# SCH_Temp-and-fan-ctrl_2026-02-23.net
KiCad netlist of a schematic drawn in EasyEDA
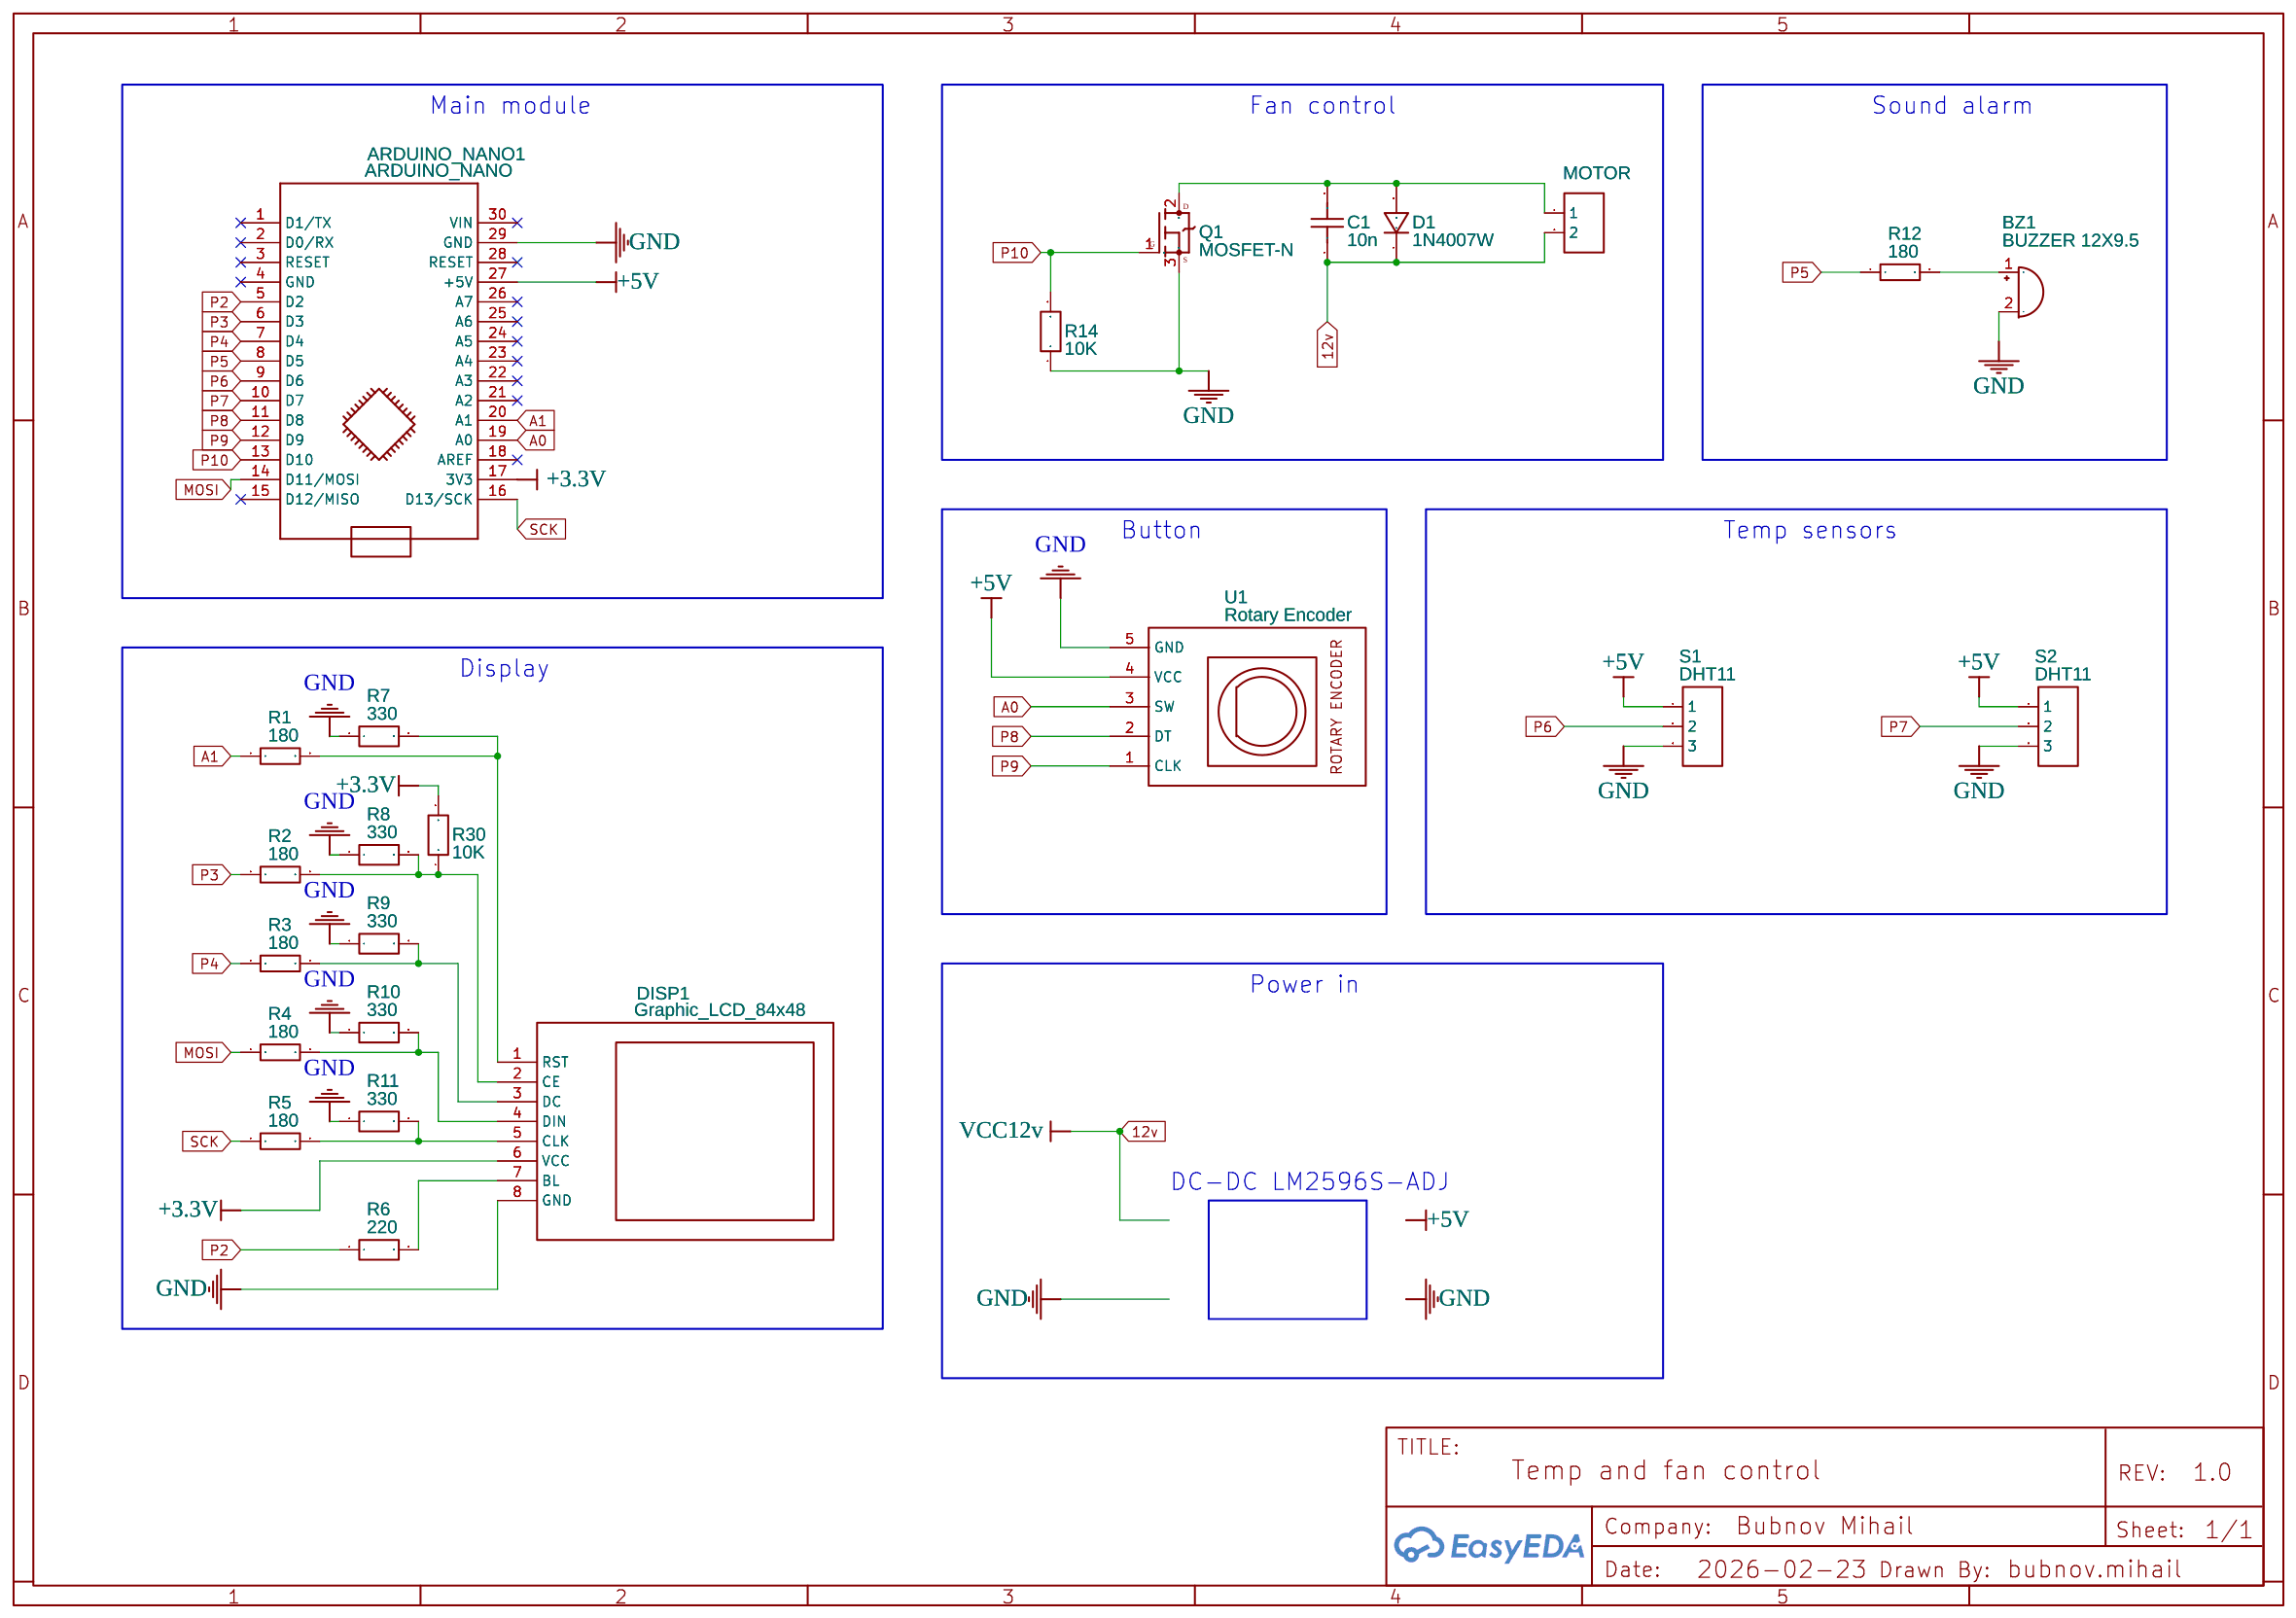
[diagram p0: schematic sheet]

(export (version "E")
  (design (tool "Eeschema 10.0.6"))
  (components
    (comp (ref "ARDUINO_NANO1") (value "ARDUINO_NANO") (libsource (lib "") (part "ARDUINO_NANO")))
    (comp (ref "BZ1") (value "BUZZER 12X9.5") (libsource (lib "") (part "BUZZER 12X9.5 FATHBOARD COPY")))
    (comp (ref "C1") (value "10n") (libsource (lib "") (part "C_0603_US")))
    (comp (ref "D1")
      (value "1N4007W")
      (fields (field (name "Manufacturer") "BLUE ROCKET"))
      (libsource (lib "") (part "1N4007W"))
    )
    (comp (ref "DISP1") (value "Graphic_LCD_84x48") (libsource (lib "") (part "Graphic_LCD_84x48")))
    (comp (ref "MOTOR") (value "1-") (libsource (lib "") (part "CONN-TH_2P-P5.00")))
    (comp (ref "Q1") (value "MOSFET-N") (libsource (lib "") (part "MOSFET-N")))
    (comp (ref "R1")
      (value "180")
      (fields (field (name "Manufacturer Part") "CFR02SJ0103A10") (field (name "Manufacturer") "UniOhm"))
      (libsource (lib "") (part "CFR02SJ0103A10"))
    )
    (comp (ref "R2")
      (value "180")
      (fields (field (name "Manufacturer Part") "CFR02SJ0103A10") (field (name "Manufacturer") "UniOhm"))
      (libsource (lib "") (part "CFR02SJ0103A10"))
    )
    (comp (ref "R3")
      (value "180")
      (fields (field (name "Manufacturer Part") "CFR02SJ0103A10") (field (name "Manufacturer") "UniOhm"))
      (libsource (lib "") (part "CFR02SJ0103A10"))
    )
    (comp (ref "R4")
      (value "180")
      (fields (field (name "Manufacturer Part") "CFR02SJ0103A10") (field (name "Manufacturer") "UniOhm"))
      (libsource (lib "") (part "CFR02SJ0103A10"))
    )
    (comp (ref "R5")
      (value "180")
      (fields (field (name "Manufacturer Part") "CFR02SJ0103A10") (field (name "Manufacturer") "UniOhm"))
      (libsource (lib "") (part "CFR02SJ0103A10"))
    )
    (comp (ref "R6")
      (value "220")
      (fields
        (field (name "Manufacturer Part") "RD 1/2WS 10K J T/B A1")
        (field (name "Manufacturer") "TyoHM")
      )
      (libsource (lib "") (part "RD 1/2WS 10K J T/B A1_1"))
    )
    (comp (ref "R7")
      (value "330")
      (fields
        (field (name "Manufacturer Part") "RD 1/2WS 10K J T/B A1")
        (field (name "Manufacturer") "TyoHM")
      )
      (libsource (lib "") (part "RD 1/2WS 10K J T/B A1_1"))
    )
    (comp (ref "R8")
      (value "330")
      (fields
        (field (name "Manufacturer Part") "RD 1/2WS 10K J T/B A1")
        (field (name "Manufacturer") "TyoHM")
      )
      (libsource (lib "") (part "RD 1/2WS 10K J T/B A1_1"))
    )
    (comp (ref "R9")
      (value "330")
      (fields
        (field (name "Manufacturer Part") "RD 1/2WS 10K J T/B A1")
        (field (name "Manufacturer") "TyoHM")
      )
      (libsource (lib "") (part "RD 1/2WS 10K J T/B A1_1"))
    )
    (comp (ref "R10")
      (value "330")
      (fields
        (field (name "Manufacturer Part") "RD 1/2WS 10K J T/B A1")
        (field (name "Manufacturer") "TyoHM")
      )
      (libsource (lib "") (part "RD 1/2WS 10K J T/B A1_1"))
    )
    (comp (ref "R11")
      (value "330")
      (fields
        (field (name "Manufacturer Part") "RD 1/2WS 10K J T/B A1")
        (field (name "Manufacturer") "TyoHM")
      )
      (libsource (lib "") (part "RD 1/2WS 10K J T/B A1_1"))
    )
    (comp (ref "R12")
      (value "180")
      (fields (field (name "Manufacturer Part") "CFR02SJ0103A10") (field (name "Manufacturer") "UniOhm"))
      (libsource (lib "") (part "CFR02SJ0103A10"))
    )
    (comp (ref "R14")
      (value "10K")
      (fields
        (field (name "Manufacturer Part") "RD 1/2WS 10K J T/B A1")
        (field (name "Manufacturer") "TyoHM")
      )
      (libsource (lib "") (part "RD 1/2WS 10K J T/B A1"))
    )
    (comp (ref "R30")
      (value "10K")
      (fields
        (field (name "Manufacturer Part") "RD 1/2WS 10K J T/B A1")
        (field (name "Manufacturer") "TyoHM")
      )
      (libsource (lib "") (part "RD 1/2WS 10K J T/B A1"))
    )
    (comp (ref "S1") (value "DHT11") (libsource (lib "") (part "HDR-F-2.54_1x3")))
    (comp (ref "S2") (value "DHT11") (libsource (lib "") (part "HDR-F-2.54_1x3")))
    (comp (ref "U1")
      (value "Rotary Encoder")
      (fields (field (name "Manufacturer Part") "KY-040"))
      (libsource (lib "") (part "Rotary Encoder"))
    )
  )
  (nets
    (net (code "1") (name "+3.3V") (class "Default")
      (node (ref "ARDUINO_NANO1") (pin "17") (pinfunction "3V3_17") (pintype "unspecified"))
      (node (ref "DISP1") (pin "6") (pinfunction "VCC_6") (pintype "passive"))
      (node (ref "R30") (pin "2") (pinfunction "2_2") (pintype "unspecified"))
    )
    (net (code "2") (name "+5V") (class "Default")
      (node (ref "ARDUINO_NANO1") (pin "27") (pinfunction "+5V_27") (pintype "unspecified"))
      (node (ref "S1") (pin "1") (pinfunction "1_1") (pintype "input"))
      (node (ref "S2") (pin "1") (pinfunction "1_1") (pintype "input"))
      (node (ref "U1") (pin "4") (pinfunction "VCC_4") (pintype "unspecified"))
    )
    (net (code "3") (name "12v") (class "Default")
      (node (ref "C1") (pin "1") (pinfunction "1_1") (pintype "unspecified"))
      (node (ref "D1") (pin "1") (pinfunction "1_1") (pintype "unspecified"))
      (node (ref "MOTOR") (pin "2") (pinfunction "2_2") (pintype "unspecified"))
    )
    (net (code "4") (name "A0") (class "Default")
      (node (ref "ARDUINO_NANO1") (pin "19") (pinfunction "A0_19") (pintype "unspecified"))
      (node (ref "U1") (pin "3") (pinfunction "SW_3") (pintype "unspecified"))
    )
    (net (code "5") (name "A1") (class "Default")
      (node (ref "ARDUINO_NANO1") (pin "20") (pinfunction "A1_20") (pintype "unspecified"))
      (node (ref "R1") (pin "1") (pinfunction "1_1") (pintype "input"))
    )
    (net (code "6") (name "GND") (class "Default")
      (node (ref "ARDUINO_NANO1") (pin "29") (pinfunction "GND_29") (pintype "unspecified"))
      (node (ref "BZ1") (pin "2") (pinfunction "-_2") (pintype "unspecified"))
      (node (ref "DISP1") (pin "8") (pinfunction "GND_8") (pintype "passive"))
      (node (ref "Q1") (pin "3") (pinfunction "S_3") (pintype "unspecified"))
      (node (ref "R10") (pin "1") (pinfunction "1_1") (pintype "unspecified"))
      (node (ref "R11") (pin "1") (pinfunction "1_1") (pintype "unspecified"))
      (node (ref "R14") (pin "1") (pinfunction "1_1") (pintype "unspecified"))
      (node (ref "R7") (pin "1") (pinfunction "1_1") (pintype "unspecified"))
      (node (ref "R8") (pin "1") (pinfunction "1_1") (pintype "unspecified"))
      (node (ref "R9") (pin "1") (pinfunction "1_1") (pintype "unspecified"))
      (node (ref "S1") (pin "3") (pinfunction "3_3") (pintype "input"))
      (node (ref "S2") (pin "3") (pinfunction "3_3") (pintype "input"))
      (node (ref "U1") (pin "5") (pinfunction "GND_5") (pintype "unspecified"))
    )
    (net (code "7") (name "MOSI") (class "Default")
      (node (ref "ARDUINO_NANO1") (pin "14") (pinfunction "D11/MOSI_14") (pintype "unspecified"))
      (node (ref "R4") (pin "1") (pinfunction "1_1") (pintype "input"))
    )
    (net (code "8") (name "Net-(BZ1-+)") (class "Default")
      (node (ref "BZ1") (pin "1") (pinfunction "+_1") (pintype "unspecified"))
      (node (ref "R12") (pin "2") (pinfunction "2_2") (pintype "input"))
    )
    (net (code "9") (name "Net-(DISP1-BL)") (class "Default")
      (node (ref "DISP1") (pin "7") (pinfunction "BL_7") (pintype "input"))
      (node (ref "R6") (pin "2") (pinfunction "2_2") (pintype "unspecified"))
    )
    (net (code "10") (name "Net-(DISP1-CE)") (class "Default")
      (node (ref "DISP1") (pin "2") (pinfunction "CE_2") (pintype "input"))
      (node (ref "R2") (pin "2") (pinfunction "2_2") (pintype "input"))
      (node (ref "R30") (pin "1") (pinfunction "1_1") (pintype "unspecified"))
      (node (ref "R8") (pin "2") (pinfunction "2_2") (pintype "unspecified"))
    )
    (net (code "11") (name "Net-(DISP1-CLK)") (class "Default")
      (node (ref "DISP1") (pin "5") (pinfunction "CLK_5") (pintype "input"))
      (node (ref "R11") (pin "2") (pinfunction "2_2") (pintype "unspecified"))
      (node (ref "R5") (pin "2") (pinfunction "2_2") (pintype "input"))
    )
    (net (code "12") (name "Net-(DISP1-DC)") (class "Default")
      (node (ref "DISP1") (pin "3") (pinfunction "DC_3") (pintype "input"))
      (node (ref "R3") (pin "2") (pinfunction "2_2") (pintype "input"))
      (node (ref "R9") (pin "2") (pinfunction "2_2") (pintype "unspecified"))
    )
    (net (code "13") (name "Net-(DISP1-DIN)") (class "Default")
      (node (ref "DISP1") (pin "4") (pinfunction "DIN_4") (pintype "input"))
      (node (ref "R10") (pin "2") (pinfunction "2_2") (pintype "unspecified"))
      (node (ref "R4") (pin "2") (pinfunction "2_2") (pintype "input"))
    )
    (net (code "14") (name "Net-(DISP1-RST)") (class "Default")
      (node (ref "DISP1") (pin "1") (pinfunction "RST_1") (pintype "input"))
      (node (ref "R1") (pin "2") (pinfunction "2_2") (pintype "input"))
      (node (ref "R7") (pin "2") (pinfunction "2_2") (pintype "unspecified"))
    )
    (net (code "15") (name "Net-(Q1-D)") (class "Default")
      (node (ref "C1") (pin "2") (pinfunction "2_2") (pintype "unspecified"))
      (node (ref "D1") (pin "2") (pinfunction "2_2") (pintype "unspecified"))
      (node (ref "MOTOR") (pin "1") (pinfunction "1_1") (pintype "unspecified"))
      (node (ref "Q1") (pin "2") (pinfunction "D_2") (pintype "unspecified"))
    )
    (net (code "16") (name "P2") (class "Default")
      (node (ref "ARDUINO_NANO1") (pin "5") (pinfunction "D2_5") (pintype "unspecified"))
      (node (ref "R6") (pin "1") (pinfunction "1_1") (pintype "unspecified"))
    )
    (net (code "17") (name "P3") (class "Default")
      (node (ref "ARDUINO_NANO1") (pin "6") (pinfunction "D3_6") (pintype "unspecified"))
      (node (ref "R2") (pin "1") (pinfunction "1_1") (pintype "input"))
    )
    (net (code "18") (name "P4") (class "Default")
      (node (ref "ARDUINO_NANO1") (pin "7") (pinfunction "D4_7") (pintype "unspecified"))
      (node (ref "R3") (pin "1") (pinfunction "1_1") (pintype "input"))
    )
    (net (code "19") (name "P5") (class "Default")
      (node (ref "ARDUINO_NANO1") (pin "8") (pinfunction "D5_8") (pintype "unspecified"))
      (node (ref "R12") (pin "1") (pinfunction "1_1") (pintype "input"))
    )
    (net (code "20") (name "P6") (class "Default")
      (node (ref "ARDUINO_NANO1") (pin "9") (pinfunction "D6_9") (pintype "unspecified"))
      (node (ref "S1") (pin "2") (pinfunction "2_2") (pintype "input"))
    )
    (net (code "21") (name "P7") (class "Default")
      (node (ref "ARDUINO_NANO1") (pin "10") (pinfunction "D7_10") (pintype "unspecified"))
      (node (ref "S2") (pin "2") (pinfunction "2_2") (pintype "input"))
    )
    (net (code "22") (name "P8") (class "Default")
      (node (ref "ARDUINO_NANO1") (pin "11") (pinfunction "D8_11") (pintype "unspecified"))
      (node (ref "U1") (pin "2") (pinfunction "DT_2") (pintype "unspecified"))
    )
    (net (code "23") (name "P9") (class "Default")
      (node (ref "ARDUINO_NANO1") (pin "12") (pinfunction "D9_12") (pintype "unspecified"))
      (node (ref "U1") (pin "1") (pinfunction "CLK_1") (pintype "unspecified"))
    )
    (net (code "24") (name "P10") (class "Default")
      (node (ref "ARDUINO_NANO1") (pin "13") (pinfunction "D10_13") (pintype "unspecified"))
      (node (ref "Q1") (pin "1") (pinfunction "G_1") (pintype "unspecified"))
      (node (ref "R14") (pin "2") (pinfunction "2_2") (pintype "unspecified"))
    )
    (net (code "25") (name "SCK") (class "Default")
      (node (ref "ARDUINO_NANO1") (pin "16") (pinfunction "D13/SCK_16") (pintype "unspecified"))
      (node (ref "R5") (pin "1") (pinfunction "1_1") (pintype "input"))
    )
    (net (code "26") (name "unconnected-(ARDUINO_NANO1-A2-Pad21)") (class "Default")
      (node (ref "ARDUINO_NANO1") (pin "21") (pinfunction "A2_21") (pintype "unspecified+no_connect"))
    )
    (net (code "27") (name "unconnected-(ARDUINO_NANO1-A3-Pad22)") (class "Default")
      (node (ref "ARDUINO_NANO1") (pin "22") (pinfunction "A3_22") (pintype "unspecified+no_connect"))
    )
    (net (code "28") (name "unconnected-(ARDUINO_NANO1-A4-Pad23)") (class "Default")
      (node (ref "ARDUINO_NANO1") (pin "23") (pinfunction "A4_23") (pintype "unspecified+no_connect"))
    )
    (net (code "29") (name "unconnected-(ARDUINO_NANO1-A5-Pad24)") (class "Default")
      (node (ref "ARDUINO_NANO1") (pin "24") (pinfunction "A5_24") (pintype "unspecified+no_connect"))
    )
    (net (code "30") (name "unconnected-(ARDUINO_NANO1-A6-Pad25)") (class "Default")
      (node (ref "ARDUINO_NANO1") (pin "25") (pinfunction "A6_25") (pintype "unspecified+no_connect"))
    )
    (net (code "31") (name "unconnected-(ARDUINO_NANO1-A7-Pad26)") (class "Default")
      (node (ref "ARDUINO_NANO1") (pin "26") (pinfunction "A7_26") (pintype "unspecified+no_connect"))
    )
    (net (code "32") (name "unconnected-(ARDUINO_NANO1-AREF-Pad18)") (class "Default")
      (node (ref "ARDUINO_NANO1") (pin "18") (pinfunction "AREF_18") (pintype "unspecified+no_connect"))
    )
    (net (code "33") (name "unconnected-(ARDUINO_NANO1-D0{slash}RX-Pad2)") (class "Default")
      (node (ref "ARDUINO_NANO1") (pin "2") (pinfunction "D0/RX_2") (pintype "unspecified+no_connect"))
    )
    (net (code "34") (name "unconnected-(ARDUINO_NANO1-D1{slash}TX-Pad1)") (class "Default")
      (node (ref "ARDUINO_NANO1") (pin "1") (pinfunction "D1/TX_1") (pintype "unspecified+no_connect"))
    )
    (net (code "35") (name "unconnected-(ARDUINO_NANO1-D12{slash}MISO-Pad15)") (class "Default")
      (node (ref "ARDUINO_NANO1") (pin "15") (pinfunction "D12/MISO_15") (pintype "unspecified+no_connect"))
    )
    (net (code "36") (name "unconnected-(ARDUINO_NANO1-GND-Pad4)") (class "Default")
      (node (ref "ARDUINO_NANO1") (pin "4") (pinfunction "GND_4") (pintype "unspecified+no_connect"))
    )
    (net (code "37") (name "unconnected-(ARDUINO_NANO1-RESET-Pad3)") (class "Default")
      (node (ref "ARDUINO_NANO1") (pin "3") (pinfunction "RESET_3") (pintype "unspecified+no_connect"))
    )
    (net (code "38") (name "unconnected-(ARDUINO_NANO1-RESET-Pad28)") (class "Default")
      (node (ref "ARDUINO_NANO1") (pin "28") (pinfunction "RESET_28") (pintype "unspecified+no_connect"))
    )
    (net (code "39") (name "unconnected-(ARDUINO_NANO1-VIN-Pad30)") (class "Default")
      (node (ref "ARDUINO_NANO1") (pin "30") (pinfunction "VIN_30") (pintype "unspecified+no_connect"))
    )
  )
)
